# Sheet03.net
KiCad netlist of a schematic drawn in Altium Designer
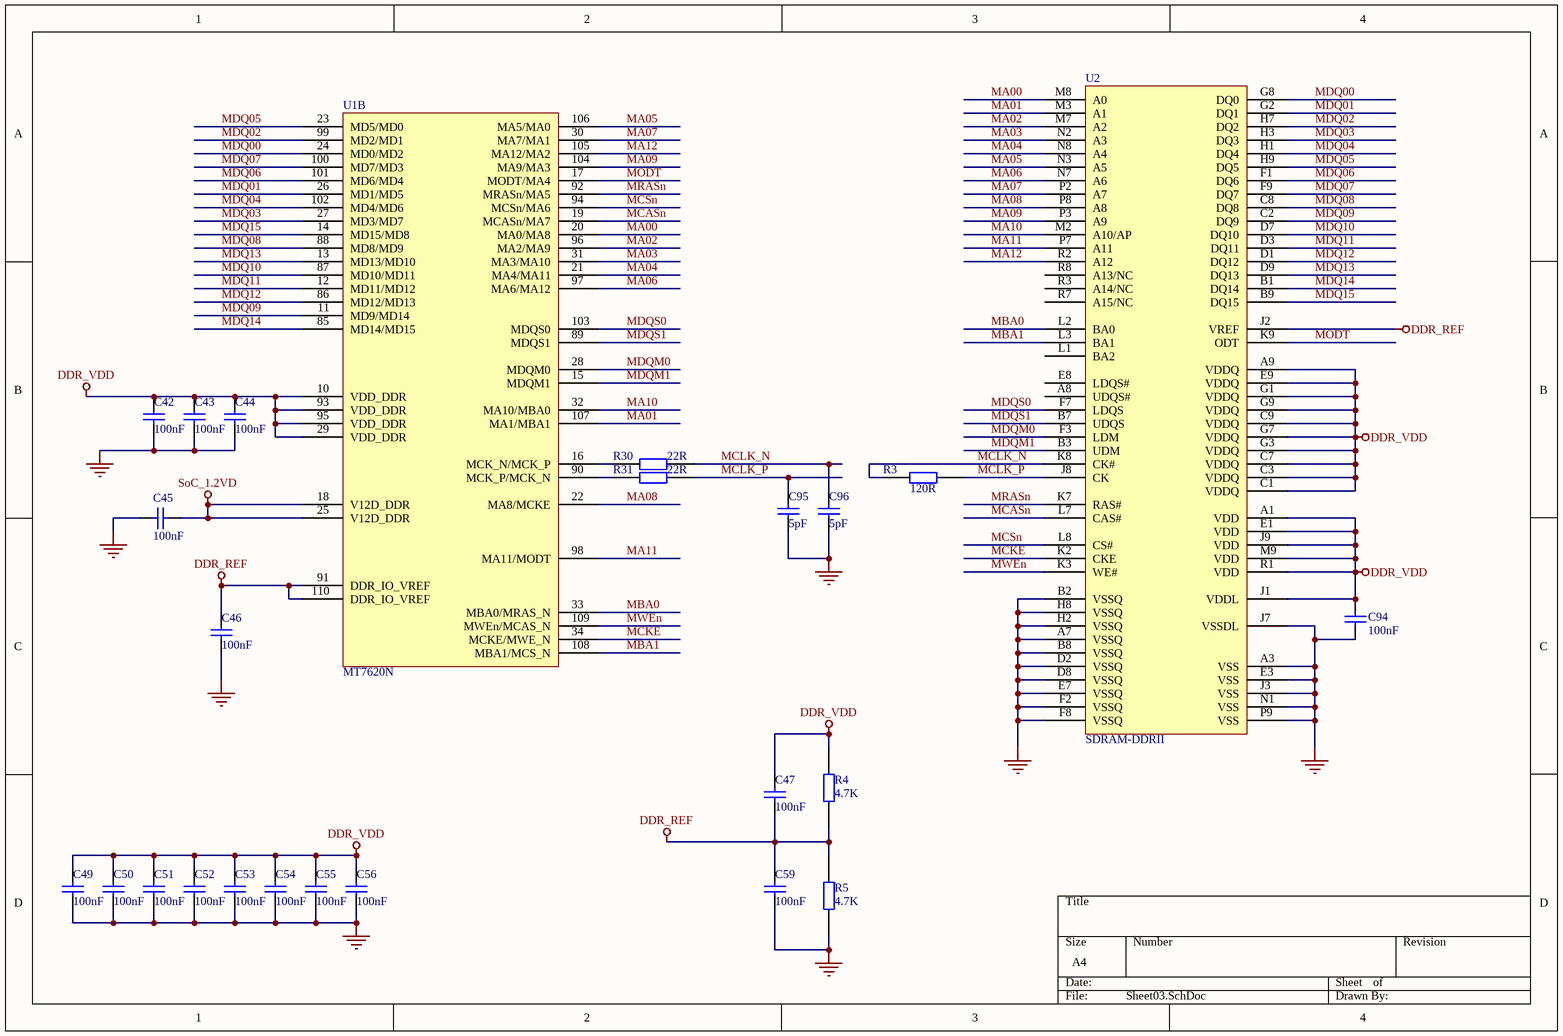
[diagram p0: Sheet03.SchDoc]

(export (version "E")
  (design (tool "Eeschema 10.0.6"))
  (components
    (comp (ref "C42")
      (value "100nF")
      (footprint "R0402")
      (description "2pF, 50V, +/-0.25pF")
      (fields
        (field (name "MANUFACTURER") "Generic Components")
        (field (name "PUBLISHER") "Altium Hobart Technology Centre")
      )
      (libsource (lib "myschlib") (part "Cap Semi"))
    )
    (comp (ref "C43")
      (value "100nF")
      (footprint "R0402")
      (description "2pF, 50V, +/-0.25pF")
      (fields
        (field (name "MANUFACTURER") "Generic Components")
        (field (name "PUBLISHER") "Altium Hobart Technology Centre")
      )
      (libsource (lib "myschlib") (part "Cap Semi"))
    )
    (comp (ref "C44")
      (value "100nF")
      (footprint "R0402")
      (description "2pF, 50V, +/-0.25pF")
      (fields
        (field (name "MANUFACTURER") "Generic Components")
        (field (name "PUBLISHER") "Altium Hobart Technology Centre")
      )
      (libsource (lib "myschlib") (part "Cap Semi"))
    )
    (comp (ref "C45")
      (value "100nF")
      (footprint "R0402")
      (description "2pF, 50V, +/-0.25pF")
      (fields
        (field (name "MANUFACTURER") "Generic Components")
        (field (name "PUBLISHER") "Altium Hobart Technology Centre")
      )
      (libsource (lib "myschlib") (part "Cap Semi"))
    )
    (comp (ref "C46")
      (value "100nF")
      (footprint "R0402")
      (description "2pF, 50V, +/-0.25pF")
      (fields
        (field (name "MANUFACTURER") "Generic Components")
        (field (name "PUBLISHER") "Altium Hobart Technology Centre")
      )
      (libsource (lib "myschlib") (part "Cap Semi"))
    )
    (comp (ref "C47")
      (value "100nF")
      (footprint "R0402")
      (description "2pF, 50V, +/-0.25pF")
      (fields
        (field (name "MANUFACTURER") "Generic Components")
        (field (name "PUBLISHER") "Altium Hobart Technology Centre")
      )
      (libsource (lib "myschlib") (part "Cap Semi"))
    )
    (comp (ref "C49")
      (value "100nF")
      (footprint "R0402")
      (description "2pF, 50V, +/-0.25pF")
      (fields
        (field (name "MANUFACTURER") "Generic Components")
        (field (name "PUBLISHER") "Altium Hobart Technology Centre")
      )
      (libsource (lib "myschlib") (part "Cap Semi"))
    )
    (comp (ref "C50")
      (value "100nF")
      (footprint "R0402")
      (description "2pF, 50V, +/-0.25pF")
      (fields
        (field (name "MANUFACTURER") "Generic Components")
        (field (name "PUBLISHER") "Altium Hobart Technology Centre")
      )
      (libsource (lib "myschlib") (part "Cap Semi"))
    )
    (comp (ref "C51")
      (value "100nF")
      (footprint "R0402")
      (description "2pF, 50V, +/-0.25pF")
      (fields
        (field (name "MANUFACTURER") "Generic Components")
        (field (name "PUBLISHER") "Altium Hobart Technology Centre")
      )
      (libsource (lib "myschlib") (part "Cap Semi"))
    )
    (comp (ref "C52")
      (value "100nF")
      (footprint "R0402")
      (description "2pF, 50V, +/-0.25pF")
      (fields
        (field (name "MANUFACTURER") "Generic Components")
        (field (name "PUBLISHER") "Altium Hobart Technology Centre")
      )
      (libsource (lib "myschlib") (part "Cap Semi"))
    )
    (comp (ref "C53")
      (value "100nF")
      (footprint "R0402")
      (description "2pF, 50V, +/-0.25pF")
      (fields
        (field (name "MANUFACTURER") "Generic Components")
        (field (name "PUBLISHER") "Altium Hobart Technology Centre")
      )
      (libsource (lib "myschlib") (part "Cap Semi"))
    )
    (comp (ref "C54")
      (value "100nF")
      (footprint "R0402")
      (description "2pF, 50V, +/-0.25pF")
      (fields
        (field (name "MANUFACTURER") "Generic Components")
        (field (name "PUBLISHER") "Altium Hobart Technology Centre")
      )
      (libsource (lib "myschlib") (part "Cap Semi"))
    )
    (comp (ref "C55")
      (value "100nF")
      (footprint "R0402")
      (description "2pF, 50V, +/-0.25pF")
      (fields
        (field (name "MANUFACTURER") "Generic Components")
        (field (name "PUBLISHER") "Altium Hobart Technology Centre")
      )
      (libsource (lib "myschlib") (part "Cap Semi"))
    )
    (comp (ref "C56")
      (value "100nF")
      (footprint "R0402")
      (description "2pF, 50V, +/-0.25pF")
      (fields
        (field (name "MANUFACTURER") "Generic Components")
        (field (name "PUBLISHER") "Altium Hobart Technology Centre")
      )
      (libsource (lib "myschlib") (part "Cap Semi"))
    )
    (comp (ref "C59")
      (value "100nF")
      (footprint "R0402")
      (description "2pF, 50V, +/-0.25pF")
      (fields
        (field (name "MANUFACTURER") "Generic Components")
        (field (name "PUBLISHER") "Altium Hobart Technology Centre")
      )
      (libsource (lib "myschlib") (part "Cap Semi"))
    )
    (comp (ref "C94")
      (value "100nF")
      (footprint "R0402")
      (description "2pF, 50V, +/-0.25pF")
      (fields
        (field (name "MANUFACTURER") "Generic Components")
        (field (name "PUBLISHER") "Altium Hobart Technology Centre")
      )
      (libsource (lib "myschlib") (part "Cap Semi"))
    )
    (comp (ref "C95")
      (value "5pF")
      (footprint "R0402")
      (description "2pF, 50V, +/-0.25pF")
      (fields
        (field (name "MANUFACTURER") "Generic Components")
        (field (name "PUBLISHER") "Altium Hobart Technology Centre")
      )
      (libsource (lib "myschlib") (part "Cap Semi"))
    )
    (comp (ref "C96")
      (value "5pF")
      (footprint "R0402")
      (description "2pF, 50V, +/-0.25pF")
      (fields
        (field (name "MANUFACTURER") "Generic Components")
        (field (name "PUBLISHER") "Altium Hobart Technology Centre")
      )
      (libsource (lib "myschlib") (part "Cap Semi"))
    )
    (comp (ref "R3") (value "120R") (footprint "R0402") (libsource (lib "") (part "RES_1")))
    (comp (ref "R4") (value "4.7K") (footprint "R0402") (libsource (lib "myschlib") (part "RES")))
    (comp (ref "R5") (value "4.7K") (footprint "R0402") (libsource (lib "myschlib") (part "RES")))
    (comp (ref "R30") (value "22R") (footprint "R0402") (libsource (lib "") (part "RES_1")))
    (comp (ref "R31") (value "22R") (footprint "R0402") (libsource (lib "") (part "RES_1")))
    (comp (ref "U1") (value "MT7620N") (footprint "QFN-148-RT") (libsource (lib "myschlib") (part "MT7620N")))
    (comp (ref "U2")
      (value "SDRAM-DDRII")
      (footprint "FPBGA-84N")
      (description "H5PS1G63, H5PS518, NT5TU32M16DG")
      (libsource (lib "myschlib") (part "SDRAM-DDRII"))
    )
  )
  (nets
    (net (code "1") (name "/MA00") (class "Default")
      (node (ref "U1") (pin "20") (pinfunction "MA0/MA8_20") (pintype "passive"))
      (node (ref "U2") (pin "M8") (pinfunction "A0_M8") (pintype "passive"))
    )
    (net (code "2") (name "/MA01") (class "Default")
      (node (ref "U1") (pin "107") (pinfunction "MA1/MBA1_107") (pintype "passive"))
      (node (ref "U2") (pin "M3") (pinfunction "A1_M3") (pintype "passive"))
    )
    (net (code "3") (name "/MA02") (class "Default")
      (node (ref "U1") (pin "96") (pinfunction "MA2/MA9_96") (pintype "passive"))
      (node (ref "U2") (pin "M7") (pinfunction "A2_M7") (pintype "passive"))
    )
    (net (code "4") (name "/MA03") (class "Default")
      (node (ref "U1") (pin "31") (pinfunction "MA3/MA10_31") (pintype "passive"))
      (node (ref "U2") (pin "N2") (pinfunction "A3_N2") (pintype "passive"))
    )
    (net (code "5") (name "/MA04") (class "Default")
      (node (ref "U1") (pin "21") (pinfunction "MA4/MA11_21") (pintype "passive"))
      (node (ref "U2") (pin "N8") (pinfunction "A4_N8") (pintype "passive"))
    )
    (net (code "6") (name "/MA05") (class "Default")
      (node (ref "U1") (pin "106") (pinfunction "MA5/MA0_106") (pintype "passive"))
      (node (ref "U2") (pin "N3") (pinfunction "A5_N3") (pintype "passive"))
    )
    (net (code "7") (name "/MA06") (class "Default")
      (node (ref "U1") (pin "97") (pinfunction "MA6/MA12_97") (pintype "passive"))
      (node (ref "U2") (pin "N7") (pinfunction "A6_N7") (pintype "passive"))
    )
    (net (code "8") (name "/MA07") (class "Default")
      (node (ref "U1") (pin "30") (pinfunction "MA7/MA1_30") (pintype "passive"))
      (node (ref "U2") (pin "P2") (pinfunction "A7_P2") (pintype "passive"))
    )
    (net (code "9") (name "/MA08") (class "Default")
      (node (ref "U1") (pin "22") (pinfunction "MA8/MCKE_22") (pintype "passive"))
      (node (ref "U2") (pin "P8") (pinfunction "A8_P8") (pintype "passive"))
    )
    (net (code "10") (name "/MA09") (class "Default")
      (node (ref "U1") (pin "104") (pinfunction "MA9/MA3_104") (pintype "passive"))
      (node (ref "U2") (pin "P3") (pinfunction "A9_P3") (pintype "passive"))
    )
    (net (code "11") (name "/MA10") (class "Default")
      (node (ref "U1") (pin "32") (pinfunction "MA10/MBA0_32") (pintype "passive"))
      (node (ref "U2") (pin "M2") (pinfunction "A10/AP_M2") (pintype "passive"))
    )
    (net (code "12") (name "/MA11") (class "Default")
      (node (ref "U1") (pin "98") (pinfunction "MA11/MODT_98") (pintype "passive"))
      (node (ref "U2") (pin "P7") (pinfunction "A11_P7") (pintype "passive"))
    )
    (net (code "13") (name "/MA12") (class "Default")
      (node (ref "U1") (pin "105") (pinfunction "MA12/MA2_105") (pintype "passive"))
      (node (ref "U2") (pin "R2") (pinfunction "A12_R2") (pintype "passive"))
    )
    (net (code "14") (name "/MBA0") (class "Default")
      (node (ref "U1") (pin "33") (pinfunction "MBA0/MRAS_N_33") (pintype "passive"))
      (node (ref "U2") (pin "L2") (pinfunction "BA0_L2") (pintype "passive"))
    )
    (net (code "15") (name "/MBA1") (class "Default")
      (node (ref "U1") (pin "108") (pinfunction "MBA1/MCS_N_108") (pintype "passive"))
      (node (ref "U2") (pin "L3") (pinfunction "BA1_L3") (pintype "passive"))
    )
    (net (code "16") (name "/MCASn") (class "Default")
      (node (ref "U1") (pin "19") (pinfunction "MCASn/MA7_19") (pintype "passive"))
      (node (ref "U2") (pin "L7") (pinfunction "CAS#_L7") (pintype "passive"))
    )
    (net (code "17") (name "/MCKE") (class "Default")
      (node (ref "U1") (pin "34") (pinfunction "MCKE/MWE_N_34") (pintype "passive"))
      (node (ref "U2") (pin "K2") (pinfunction "CKE_K2") (pintype "passive"))
    )
    (net (code "18") (name "/MCLK_N") (class "Default")
      (node (ref "C96") (pin "2") (pinfunction "2_2") (pintype "passive"))
      (node (ref "R3") (pin "2") (pinfunction "2_2") (pintype "passive"))
      (node (ref "R30") (pin "1") (pinfunction "1_1") (pintype "passive"))
      (node (ref "U2") (pin "K8") (pinfunction "CK#_K8") (pintype "passive"))
    )
    (net (code "19") (name "/MCLK_P") (class "Default")
      (node (ref "C95") (pin "2") (pinfunction "2_2") (pintype "passive"))
      (node (ref "R3") (pin "1") (pinfunction "1_1") (pintype "passive"))
      (node (ref "R31") (pin "1") (pinfunction "1_1") (pintype "passive"))
      (node (ref "U2") (pin "J8") (pinfunction "CK_J8") (pintype "passive"))
    )
    (net (code "20") (name "/MCSn") (class "Default")
      (node (ref "U1") (pin "94") (pinfunction "MCSn/MA6_94") (pintype "passive"))
      (node (ref "U2") (pin "L8") (pinfunction "CS#_L8") (pintype "passive"))
    )
    (net (code "21") (name "/MDQ00") (class "Default")
      (node (ref "U1") (pin "24") (pinfunction "MD0/MD2_24") (pintype "passive"))
      (node (ref "U2") (pin "G8") (pinfunction "DQ0_G8") (pintype "passive"))
    )
    (net (code "22") (name "/MDQ01") (class "Default")
      (node (ref "U1") (pin "26") (pinfunction "MD1/MD5_26") (pintype "passive"))
      (node (ref "U2") (pin "G2") (pinfunction "DQ1_G2") (pintype "passive"))
    )
    (net (code "23") (name "/MDQ02") (class "Default")
      (node (ref "U1") (pin "99") (pinfunction "MD2/MD1_99") (pintype "passive"))
      (node (ref "U2") (pin "H7") (pinfunction "DQ2_H7") (pintype "passive"))
    )
    (net (code "24") (name "/MDQ03") (class "Default")
      (node (ref "U1") (pin "27") (pinfunction "MD3/MD7_27") (pintype "passive"))
      (node (ref "U2") (pin "H3") (pinfunction "DQ3_H3") (pintype "passive"))
    )
    (net (code "25") (name "/MDQ04") (class "Default")
      (node (ref "U1") (pin "102") (pinfunction "MD4/MD6_102") (pintype "passive"))
      (node (ref "U2") (pin "H1") (pinfunction "DQ4_H1") (pintype "passive"))
    )
    (net (code "26") (name "/MDQ05") (class "Default")
      (node (ref "U1") (pin "23") (pinfunction "MD5/MD0_23") (pintype "passive"))
      (node (ref "U2") (pin "H9") (pinfunction "DQ5_H9") (pintype "passive"))
    )
    (net (code "27") (name "/MDQ06") (class "Default")
      (node (ref "U1") (pin "101") (pinfunction "MD6/MD4_101") (pintype "passive"))
      (node (ref "U2") (pin "F1") (pinfunction "DQ6_F1") (pintype "passive"))
    )
    (net (code "28") (name "/MDQ07") (class "Default")
      (node (ref "U1") (pin "100") (pinfunction "MD7/MD3_100") (pintype "passive"))
      (node (ref "U2") (pin "F9") (pinfunction "DQ7_F9") (pintype "passive"))
    )
    (net (code "29") (name "/MDQ08") (class "Default")
      (node (ref "U1") (pin "88") (pinfunction "MD8/MD9_88") (pintype "passive"))
      (node (ref "U2") (pin "C8") (pinfunction "DQ8_C8") (pintype "passive"))
    )
    (net (code "30") (name "/MDQ09") (class "Default")
      (node (ref "U1") (pin "11") (pinfunction "MD9/MD14_11") (pintype "passive"))
      (node (ref "U2") (pin "C2") (pinfunction "DQ9_C2") (pintype "passive"))
    )
    (net (code "31") (name "/MDQ10") (class "Default")
      (node (ref "U1") (pin "87") (pinfunction "MD10/MD11_87") (pintype "passive"))
      (node (ref "U2") (pin "D7") (pinfunction "DQ10_D7") (pintype "passive"))
    )
    (net (code "32") (name "/MDQ11") (class "Default")
      (node (ref "U1") (pin "12") (pinfunction "MD11/MD12_12") (pintype "passive"))
      (node (ref "U2") (pin "D3") (pinfunction "DQ11_D3") (pintype "passive"))
    )
    (net (code "33") (name "/MDQ12") (class "Default")
      (node (ref "U1") (pin "86") (pinfunction "MD12/MD13_86") (pintype "passive"))
      (node (ref "U2") (pin "D1") (pinfunction "DQ12_D1") (pintype "passive"))
    )
    (net (code "34") (name "/MDQ13") (class "Default")
      (node (ref "U1") (pin "13") (pinfunction "MD13/MD10_13") (pintype "passive"))
      (node (ref "U2") (pin "D9") (pinfunction "DQ13_D9") (pintype "passive"))
    )
    (net (code "35") (name "/MDQ14") (class "Default")
      (node (ref "U1") (pin "85") (pinfunction "MD14/MD15_85") (pintype "passive"))
      (node (ref "U2") (pin "B1") (pinfunction "DQ14_B1") (pintype "passive"))
    )
    (net (code "36") (name "/MDQ15") (class "Default")
      (node (ref "U1") (pin "14") (pinfunction "MD15/MD8_14") (pintype "passive"))
      (node (ref "U2") (pin "B9") (pinfunction "DQ15_B9") (pintype "passive"))
    )
    (net (code "37") (name "/MDQM0") (class "Default")
      (node (ref "U1") (pin "28") (pinfunction "MDQM0_28") (pintype "passive"))
      (node (ref "U2") (pin "F3") (pinfunction "LDM_F3") (pintype "passive"))
    )
    (net (code "38") (name "/MDQM1") (class "Default")
      (node (ref "U1") (pin "15") (pinfunction "MDQM1_15") (pintype "passive"))
      (node (ref "U2") (pin "B3") (pinfunction "UDM_B3") (pintype "passive"))
    )
    (net (code "39") (name "/MDQS0") (class "Default")
      (node (ref "U1") (pin "103") (pinfunction "MDQS0_103") (pintype "passive"))
      (node (ref "U2") (pin "F7") (pinfunction "LDQS_F7") (pintype "passive"))
    )
    (net (code "40") (name "/MDQS1") (class "Default")
      (node (ref "U1") (pin "89") (pinfunction "MDQS1_89") (pintype "passive"))
      (node (ref "U2") (pin "B7") (pinfunction "UDQS_B7") (pintype "passive"))
    )
    (net (code "41") (name "/MODT") (class "Default")
      (node (ref "U1") (pin "17") (pinfunction "MODT/MA4_17") (pintype "passive"))
      (node (ref "U2") (pin "K9") (pinfunction "ODT_K9") (pintype "passive"))
    )
    (net (code "42") (name "/MRASn") (class "Default")
      (node (ref "U1") (pin "92") (pinfunction "MRASn/MA5_92") (pintype "passive"))
      (node (ref "U2") (pin "K7") (pinfunction "RAS#_K7") (pintype "passive"))
    )
    (net (code "43") (name "/MWEn") (class "Default")
      (node (ref "U1") (pin "109") (pinfunction "MWEn/MCAS_N_109") (pintype "passive"))
      (node (ref "U2") (pin "K3") (pinfunction "WE#_K3") (pintype "passive"))
    )
    (net (code "44") (name "DDR_REF") (class "Default")
      (node (ref "C46") (pin "2") (pinfunction "2_2") (pintype "passive"))
      (node (ref "C47") (pin "1") (pinfunction "1_1") (pintype "passive"))
      (node (ref "C59") (pin "2") (pinfunction "2_2") (pintype "passive"))
      (node (ref "R4") (pin "1") (pinfunction "1_1") (pintype "passive"))
      (node (ref "R5") (pin "2") (pinfunction "2_2") (pintype "passive"))
      (node (ref "U1") (pin "110") (pinfunction "DDR_IO_VREF_110") (pintype "passive"))
      (node (ref "U1") (pin "91") (pinfunction "DDR_IO_VREF_91") (pintype "passive"))
      (node (ref "U2") (pin "J2") (pinfunction "VREF_J2") (pintype "passive"))
    )
    (net (code "45") (name "DDR_VDD") (class "Default")
      (node (ref "C42") (pin "2") (pinfunction "2_2") (pintype "passive"))
      (node (ref "C43") (pin "2") (pinfunction "2_2") (pintype "passive"))
      (node (ref "C44") (pin "2") (pinfunction "2_2") (pintype "passive"))
      (node (ref "C47") (pin "2") (pinfunction "2_2") (pintype "passive"))
      (node (ref "C49") (pin "2") (pinfunction "2_2") (pintype "passive"))
      (node (ref "C50") (pin "2") (pinfunction "2_2") (pintype "passive"))
      (node (ref "C51") (pin "2") (pinfunction "2_2") (pintype "passive"))
      (node (ref "C52") (pin "2") (pinfunction "2_2") (pintype "passive"))
      (node (ref "C53") (pin "2") (pinfunction "2_2") (pintype "passive"))
      (node (ref "C54") (pin "2") (pinfunction "2_2") (pintype "passive"))
      (node (ref "C55") (pin "2") (pinfunction "2_2") (pintype "passive"))
      (node (ref "C56") (pin "2") (pinfunction "2_2") (pintype "passive"))
      (node (ref "C94") (pin "1") (pinfunction "1_1") (pintype "passive"))
      (node (ref "R4") (pin "2") (pinfunction "2_2") (pintype "passive"))
      (node (ref "U1") (pin "10") (pinfunction "VDD_DDR_10") (pintype "passive"))
      (node (ref "U1") (pin "29") (pinfunction "VDD_DDR_29") (pintype "passive"))
      (node (ref "U1") (pin "93") (pinfunction "VDD_DDR_93") (pintype "passive"))
      (node (ref "U1") (pin "95") (pinfunction "VDD_DDR_95") (pintype "passive"))
      (node (ref "U2") (pin "A1") (pinfunction "VDD_A1") (pintype "passive"))
      (node (ref "U2") (pin "A9") (pinfunction "VDDQ_A9") (pintype "passive"))
      (node (ref "U2") (pin "C1") (pinfunction "VDDQ_C1") (pintype "passive"))
      (node (ref "U2") (pin "C3") (pinfunction "VDDQ_C3") (pintype "passive"))
      (node (ref "U2") (pin "C7") (pinfunction "VDDQ_C7") (pintype "passive"))
      (node (ref "U2") (pin "C9") (pinfunction "VDDQ_C9") (pintype "passive"))
      (node (ref "U2") (pin "E1") (pinfunction "VDD_E1") (pintype "passive"))
      (node (ref "U2") (pin "E9") (pinfunction "VDDQ_E9") (pintype "passive"))
      (node (ref "U2") (pin "G1") (pinfunction "VDDQ_G1") (pintype "passive"))
      (node (ref "U2") (pin "G3") (pinfunction "VDDQ_G3") (pintype "passive"))
      (node (ref "U2") (pin "G7") (pinfunction "VDDQ_G7") (pintype "passive"))
      (node (ref "U2") (pin "G9") (pinfunction "VDDQ_G9") (pintype "passive"))
      (node (ref "U2") (pin "J1") (pinfunction "VDDL_J1") (pintype "passive"))
      (node (ref "U2") (pin "J9") (pinfunction "VDD_J9") (pintype "passive"))
      (node (ref "U2") (pin "M9") (pinfunction "VDD_M9") (pintype "passive"))
      (node (ref "U2") (pin "R1") (pinfunction "VDD_R1") (pintype "passive"))
    )
    (net (code "46") (name "GND") (class "Default")
      (node (ref "C42") (pin "1") (pinfunction "1_1") (pintype "passive"))
      (node (ref "C43") (pin "1") (pinfunction "1_1") (pintype "passive"))
      (node (ref "C44") (pin "1") (pinfunction "1_1") (pintype "passive"))
      (node (ref "C45") (pin "2") (pinfunction "2_2") (pintype "passive"))
      (node (ref "C46") (pin "1") (pinfunction "1_1") (pintype "passive"))
      (node (ref "C49") (pin "1") (pinfunction "1_1") (pintype "passive"))
      (node (ref "C50") (pin "1") (pinfunction "1_1") (pintype "passive"))
      (node (ref "C51") (pin "1") (pinfunction "1_1") (pintype "passive"))
      (node (ref "C52") (pin "1") (pinfunction "1_1") (pintype "passive"))
      (node (ref "C53") (pin "1") (pinfunction "1_1") (pintype "passive"))
      (node (ref "C54") (pin "1") (pinfunction "1_1") (pintype "passive"))
      (node (ref "C55") (pin "1") (pinfunction "1_1") (pintype "passive"))
      (node (ref "C56") (pin "1") (pinfunction "1_1") (pintype "passive"))
      (node (ref "C59") (pin "1") (pinfunction "1_1") (pintype "passive"))
      (node (ref "C94") (pin "2") (pinfunction "2_2") (pintype "passive"))
      (node (ref "C95") (pin "1") (pinfunction "1_1") (pintype "passive"))
      (node (ref "C96") (pin "1") (pinfunction "1_1") (pintype "passive"))
      (node (ref "R5") (pin "1") (pinfunction "1_1") (pintype "passive"))
      (node (ref "U2") (pin "A3") (pinfunction "VSS_A3") (pintype "passive"))
      (node (ref "U2") (pin "A7") (pinfunction "VSSQ_A7") (pintype "passive"))
      (node (ref "U2") (pin "B2") (pinfunction "VSSQ_B2") (pintype "passive"))
      (node (ref "U2") (pin "B8") (pinfunction "VSSQ_B8") (pintype "passive"))
      (node (ref "U2") (pin "D2") (pinfunction "VSSQ_D2") (pintype "passive"))
      (node (ref "U2") (pin "D8") (pinfunction "VSSQ_D8") (pintype "passive"))
      (node (ref "U2") (pin "E3") (pinfunction "VSS_E3") (pintype "passive"))
      (node (ref "U2") (pin "E7") (pinfunction "VSSQ_E7") (pintype "passive"))
      (node (ref "U2") (pin "F2") (pinfunction "VSSQ_F2") (pintype "passive"))
      (node (ref "U2") (pin "F8") (pinfunction "VSSQ_F8") (pintype "passive"))
      (node (ref "U2") (pin "H2") (pinfunction "VSSQ_H2") (pintype "passive"))
      (node (ref "U2") (pin "H8") (pinfunction "VSSQ_H8") (pintype "passive"))
      (node (ref "U2") (pin "J3") (pinfunction "VSS_J3") (pintype "passive"))
      (node (ref "U2") (pin "J7") (pinfunction "VSSDL_J7") (pintype "passive"))
      (node (ref "U2") (pin "N1") (pinfunction "VSS_N1") (pintype "passive"))
      (node (ref "U2") (pin "P9") (pinfunction "VSS_P9") (pintype "passive"))
    )
    (net (code "47") (name "Net-(U1B-MCK_N{slash}MCK_P)") (class "Default")
      (node (ref "R30") (pin "2") (pinfunction "2_2") (pintype "passive"))
      (node (ref "U1") (pin "16") (pinfunction "MCK_N/MCK_P_16") (pintype "passive"))
    )
    (net (code "48") (name "Net-(U1B-MCK_P{slash}MCK_N)") (class "Default")
      (node (ref "R31") (pin "2") (pinfunction "2_2") (pintype "passive"))
      (node (ref "U1") (pin "90") (pinfunction "MCK_P/MCK_N_90") (pintype "passive"))
    )
    (net (code "49") (name "SoC_1.2VD") (class "Default")
      (node (ref "C45") (pin "1") (pinfunction "1_1") (pintype "passive"))
      (node (ref "U1") (pin "18") (pinfunction "V12D_DDR_18") (pintype "passive"))
      (node (ref "U1") (pin "25") (pinfunction "V12D_DDR_25") (pintype "passive"))
    )
    (net (code "50") (name "unconnected-(U2-A13{slash}NC-PadR8)") (class "Default")
      (node (ref "U2") (pin "R8") (pinfunction "A13/NC_R8") (pintype "passive"))
    )
    (net (code "51") (name "unconnected-(U2-A14{slash}NC-PadR3)") (class "Default")
      (node (ref "U2") (pin "R3") (pinfunction "A14/NC_R3") (pintype "passive"))
    )
    (net (code "52") (name "unconnected-(U2-A15{slash}NC-PadR7)") (class "Default")
      (node (ref "U2") (pin "R7") (pinfunction "A15/NC_R7") (pintype "passive"))
    )
    (net (code "53") (name "unconnected-(U2-BA2-PadL1)") (class "Default")
      (node (ref "U2") (pin "L1") (pinfunction "BA2_L1") (pintype "passive"))
    )
    (net (code "54") (name "unconnected-(U2-LDQS#-PadE8)") (class "Default")
      (node (ref "U2") (pin "E8") (pinfunction "LDQS#_E8") (pintype "passive"))
    )
    (net (code "55") (name "unconnected-(U2-UDQS#-PadA8)") (class "Default")
      (node (ref "U2") (pin "A8") (pinfunction "UDQS#_A8") (pintype "passive"))
    )
  )
)
